# BUZZER.net
KiCad netlist of a schematic drawn in Altium Designer
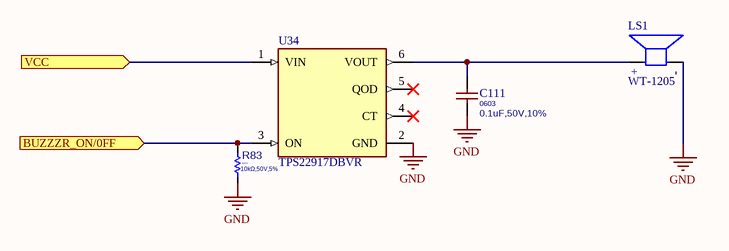
[diagram p0: BUZZER.SchDoc]

(export (version "E")
  (design (tool "Eeschema 10.0.6"))
  (components
    (comp (ref "C111")
      (value "0.1uF,50V,10%")
      (footprint "C0603")
      (description "CAP CER 0.1UF 50V X7R 0603")
      (fields
        (field (name "MANUFACTURER") "Murata Electronics")
        (field (name "MPN") "GCM188R71H104KA57J")
        (field (name "PACKAGE") "0603")
      )
      (libsource (lib "RCL") (part "GCM188R71H104KA57J"))
    )
    (comp (ref "LS1")
      (value "WT-1205")
      (footprint "XDCR_AT-1224-TWT-5V-2-R")
      (fields (field (name "MP") "AT-1224-TWT-5V-2-R"))
      (libsource (lib "LED") (part "WT-1205"))
    )
    (comp (ref "R83")
      (value "10kΩ,50V,5%")
      (footprint "R0402")
      (description "62.5mW Thick Film Resistors 50V ±100ppm/℃ ±5% 10kΩ 0402 Chip Resistor - Surface Mount ROHS")
      (fields
        (field (name "MANUFACTURER") "YAGEO")
        (field (name "MPN") "RC0402JR-0710KL")
        (field (name "PACKAGE") "0402")
      )
      (libsource (lib "RCL") (part "RC0402JR-0710KL"))
    )
    (comp (ref "U34")
      (value "TPS22917DBVR")
      (footprint "SOT95P280X145-6N")
      (description "5.5-V, 2-A, 80-mÎ© , 10-nA leakage load switch adj. rise time and adj output discharge")
      (fields (field (name "MF") "Texas Instruments"))
      (libsource (lib "IC") (part "TPS22917DBVR"))
    )
  )
  (nets
    (net (code "1") (name "/BUZZZR_ON{slash}0FF") (class "Default")
      (node (ref "R83") (pin "2") (pinfunction "2_2") (pintype "passive"))
      (node (ref "U34") (pin "3") (pinfunction "ON_3") (pintype "input"))
    )
    (net (code "2") (name "/VCC") (class "Default")
      (node (ref "U34") (pin "1") (pinfunction "VIN_1") (pintype "input"))
    )
    (net (code "3") (name "GND") (class "Default")
      (node (ref "C111") (pin "1") (pinfunction "1_1") (pintype "passive"))
      (node (ref "LS1") (pin "N") (pinfunction "N_N") (pintype "passive"))
      (node (ref "R83") (pin "1") (pinfunction "1_1") (pintype "passive"))
      (node (ref "U34") (pin "2") (pinfunction "GND_2") (pintype "power_in"))
    )
    (net (code "4") (name "Net-(U34-VOUT)") (class "Default")
      (node (ref "C111") (pin "2") (pinfunction "2_2") (pintype "passive"))
      (node (ref "LS1") (pin "P") (pinfunction "P_P") (pintype "passive"))
      (node (ref "U34") (pin "6") (pinfunction "VOUT_6") (pintype "output"))
    )
    (net (code "5") (name "unconnected-(U34-CT-Pad4)") (class "Default")
      (node (ref "U34") (pin "4") (pinfunction "CT_4") (pintype "output+no_connect"))
    )
    (net (code "6") (name "unconnected-(U34-QOD-Pad5)") (class "Default")
      (node (ref "U34") (pin "5") (pinfunction "QOD_5") (pintype "output+no_connect"))
    )
  )
)
